# Esquematico_Blue_Pill.net
KiCad netlist of a schematic drawn in EAGLE
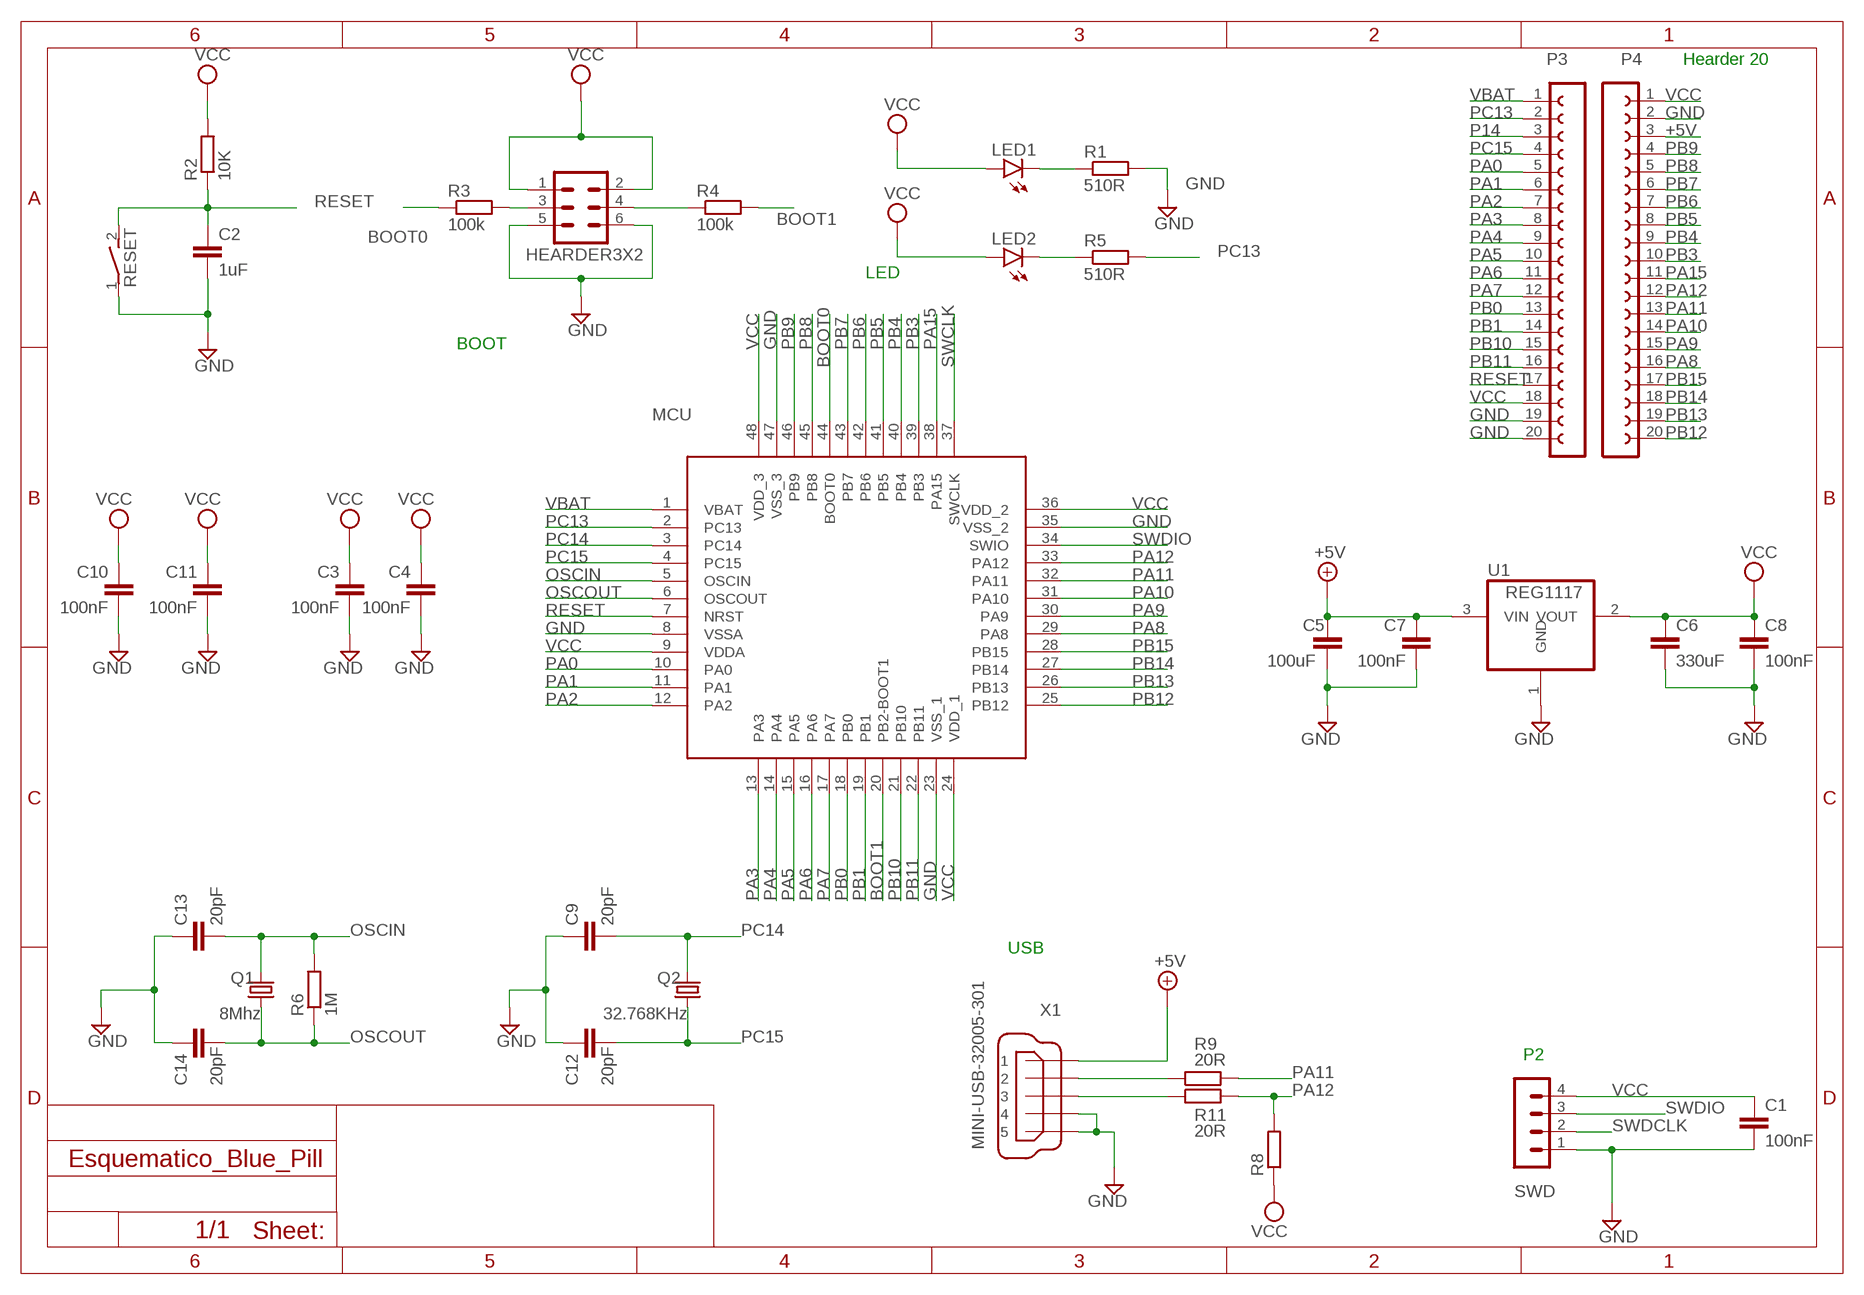
[diagram p0: schematic, sheet 1]

(export (version "E")
  (design (tool "Eeschema 10.0.6"))
  (components
    (comp (ref "C1")
      (value "100nF")
      (footprint "eagle-import:C2.5-2")
      (libsource (lib "eagle-import") (part "C2.5/2"))
    )
    (comp (ref "C2")
      (value "1uF")
      (footprint "eagle-import:C2.5-3")
      (libsource (lib "eagle-import") (part "C2,5-3"))
    )
    (comp (ref "C3")
      (value "100nF")
      (footprint "eagle-import:C2.5-2")
      (libsource (lib "eagle-import") (part "C2.5/2"))
    )
    (comp (ref "C4")
      (value "100nF")
      (footprint "eagle-import:C2.5-2")
      (libsource (lib "eagle-import") (part "C2.5/2"))
    )
    (comp (ref "C5")
      (value "100uF")
      (footprint "eagle-import:C2.5-2")
      (libsource (lib "eagle-import") (part "C2.5/2"))
    )
    (comp (ref "C6")
      (value "330uF")
      (footprint "eagle-import:C2.5-2")
      (libsource (lib "eagle-import") (part "C2.5/2"))
    )
    (comp (ref "C7")
      (value "100nF")
      (footprint "eagle-import:C2.5-2")
      (libsource (lib "eagle-import") (part "C2.5/2"))
    )
    (comp (ref "C8")
      (value "100nF")
      (footprint "eagle-import:C2.5-2")
      (libsource (lib "eagle-import") (part "C2.5/2"))
    )
    (comp (ref "C9")
      (value "20pF")
      (footprint "eagle-import:C2.5-2")
      (libsource (lib "eagle-import") (part "C2.5/2"))
    )
    (comp (ref "C10")
      (value "100nF")
      (footprint "eagle-import:C2.5-2")
      (libsource (lib "eagle-import") (part "C2.5/2"))
    )
    (comp (ref "C11")
      (value "100nF")
      (footprint "eagle-import:C2.5-2")
      (libsource (lib "eagle-import") (part "C2.5/2"))
    )
    (comp (ref "C12")
      (value "20pF")
      (footprint "eagle-import:C2.5-2")
      (libsource (lib "eagle-import") (part "C2.5/2"))
    )
    (comp (ref "C13")
      (value "20pF")
      (footprint "eagle-import:C2.5-2")
      (libsource (lib "eagle-import") (part "C2.5/2"))
    )
    (comp (ref "C14")
      (value "20pF")
      (footprint "eagle-import:C2.5-2")
      (libsource (lib "eagle-import") (part "C2.5/2"))
    )
    (comp (ref "HEARDER3X2")
      (value "MA03-2")
      (footprint "eagle-import:MA03-2")
      (libsource (lib "eagle-import") (part "MA03-2"))
    )
    (comp (ref "LED1")
      (value "LED3MM")
      (footprint "eagle-import:LED3MM")
      (libsource (lib "eagle-import") (part "LED3MM"))
    )
    (comp (ref "LED2")
      (value "LED3MM")
      (footprint "eagle-import:LED3MM")
      (libsource (lib "eagle-import") (part "LED3MM"))
    )
    (comp (ref "MCU")
      (value "STM32F103C8T6F103C8T6")
      (footprint "eagle-import:STM32")
      (libsource (lib "eagle-import") (part "STM32F103C8T6F103C8T6"))
    )
    (comp (ref "P3")
      (value "FE20-1")
      (footprint "eagle-import:FE20")
      (libsource (lib "eagle-import") (part "FE20-1"))
    )
    (comp (ref "P4")
      (value "FE20-1")
      (footprint "eagle-import:FE20")
      (libsource (lib "eagle-import") (part "FE20-1"))
    )
    (comp (ref "Q1")
      (value "8Mhz")
      (footprint "eagle-import:HC49_S")
      (libsource (lib "eagle-import") (part "CRYSTALHC49S"))
    )
    (comp (ref "Q2")
      (value "32.768KHz")
      (footprint "eagle-import:HC49_S")
      (libsource (lib "eagle-import") (part "CRYSTALHC49S"))
    )
    (comp (ref "R1")
      (value "510R")
      (footprint "eagle-import:0204_5")
      (libsource (lib "eagle-import") (part "R-EU_0204/5"))
    )
    (comp (ref "R2")
      (value "10K")
      (footprint "eagle-import:0204_7")
      (libsource (lib "eagle-import") (part "R-EU_0204/7"))
    )
    (comp (ref "R3")
      (value "100k")
      (footprint "eagle-import:0204_5")
      (libsource (lib "eagle-import") (part "R-EU_0204/5"))
    )
    (comp (ref "R4")
      (value "100k")
      (footprint "eagle-import:0204_5")
      (libsource (lib "eagle-import") (part "R-EU_0204/5"))
    )
    (comp (ref "R5")
      (value "510R")
      (footprint "eagle-import:0204_5")
      (libsource (lib "eagle-import") (part "R-EU_0204/5"))
    )
    (comp (ref "R6")
      (value "1M")
      (footprint "eagle-import:0204_5")
      (libsource (lib "eagle-import") (part "R-EU_0204/5"))
    )
    (comp (ref "R8")
      (value "R-EU_0204/5")
      (footprint "eagle-import:0204_5")
      (libsource (lib "eagle-import") (part "R-EU_0204/5"))
    )
    (comp (ref "R9")
      (value "20R")
      (footprint "eagle-import:0204_5")
      (libsource (lib "eagle-import") (part "R-EU_0204/5"))
    )
    (comp (ref "R11")
      (value "20R")
      (footprint "eagle-import:0204_5")
      (libsource (lib "eagle-import") (part "R-EU_0204/5"))
    )
    (comp (ref "RESET")
      (value "DS01E")
      (footprint "eagle-import:DS-01")
      (libsource (lib "eagle-import") (part "DS01E"))
    )
    (comp (ref "SWD")
      (value "MA04-1")
      (footprint "eagle-import:MA04-1")
      (libsource (lib "eagle-import") (part "MA04-1"))
    )
    (comp (ref "U1")
      (value "REG1117")
      (footprint "eagle-import:SOT223")
      (libsource (lib "eagle-import") (part "REG1117"))
    )
    (comp (ref "X1")
      (value "MINI-USB-32005-301")
      (footprint "eagle-import:32005-301")
      (libsource (lib "eagle-import") (part "MINI-USB-32005-301"))
    )
  )
  (nets
    (net (code "1") (name "+5V") (class "Default")
      (node (ref "C5") (pin "1") (pinfunction "1_1") (pintype "passive"))
      (node (ref "C7") (pin "1") (pinfunction "1_1") (pintype "passive"))
      (node (ref "P4") (pin "3") (pinfunction "3_3") (pintype "passive"))
      (node (ref "U1") (pin "3") (pinfunction "VIN_3") (pintype "input"))
      (node (ref "X1") (pin "1") (pinfunction "1_1") (pintype "passive"))
    )
    (net (code "2") (name "/BOOT0") (class "Default")
      (node (ref "MCU") (pin "44") (pinfunction "BOOT0_44") (pintype "bidirectional"))
      (node (ref "R3") (pin "1") (pinfunction "1_1") (pintype "passive"))
    )
    (net (code "3") (name "/BOOT1") (class "Default")
      (node (ref "MCU") (pin "20") (pinfunction "PB2-BOOT1_20") (pintype "bidirectional"))
      (node (ref "R4") (pin "2") (pinfunction "2_2") (pintype "passive"))
    )
    (net (code "4") (name "/OSCIN") (class "Default")
      (node (ref "C13") (pin "2") (pinfunction "2_2") (pintype "passive"))
      (node (ref "MCU") (pin "5") (pinfunction "OSCIN_5") (pintype "bidirectional"))
      (node (ref "Q1") (pin "2") (pinfunction "2_2") (pintype "passive"))
      (node (ref "R6") (pin "2") (pinfunction "2_2") (pintype "passive"))
    )
    (net (code "5") (name "/OSCOUT") (class "Default")
      (node (ref "C14") (pin "2") (pinfunction "2_2") (pintype "passive"))
      (node (ref "MCU") (pin "6") (pinfunction "OSCOUT_6") (pintype "bidirectional"))
      (node (ref "Q1") (pin "1") (pinfunction "1_1") (pintype "passive"))
      (node (ref "R6") (pin "1") (pinfunction "1_1") (pintype "passive"))
    )
    (net (code "6") (name "/P14") (class "Default")
      (node (ref "P3") (pin "3") (pinfunction "3_3") (pintype "passive"))
    )
    (net (code "7") (name "/PA0") (class "Default")
      (node (ref "MCU") (pin "10") (pinfunction "PA0_10") (pintype "bidirectional"))
      (node (ref "P3") (pin "5") (pinfunction "5_5") (pintype "passive"))
    )
    (net (code "8") (name "/PA1") (class "Default")
      (node (ref "MCU") (pin "11") (pinfunction "PA1_11") (pintype "bidirectional"))
      (node (ref "P3") (pin "6") (pinfunction "6_6") (pintype "passive"))
    )
    (net (code "9") (name "/PA2") (class "Default")
      (node (ref "MCU") (pin "12") (pinfunction "PA2_12") (pintype "bidirectional"))
      (node (ref "P3") (pin "7") (pinfunction "7_7") (pintype "passive"))
    )
    (net (code "10") (name "/PA3") (class "Default")
      (node (ref "MCU") (pin "13") (pinfunction "PA3_13") (pintype "bidirectional"))
      (node (ref "P3") (pin "8") (pinfunction "8_8") (pintype "passive"))
    )
    (net (code "11") (name "/PA4") (class "Default")
      (node (ref "MCU") (pin "14") (pinfunction "PA4_14") (pintype "bidirectional"))
      (node (ref "P3") (pin "9") (pinfunction "9_9") (pintype "passive"))
    )
    (net (code "12") (name "/PA5") (class "Default")
      (node (ref "MCU") (pin "15") (pinfunction "PA5_15") (pintype "bidirectional"))
      (node (ref "P3") (pin "10") (pinfunction "10_10") (pintype "passive"))
    )
    (net (code "13") (name "/PA6") (class "Default")
      (node (ref "MCU") (pin "16") (pinfunction "PA6_16") (pintype "bidirectional"))
      (node (ref "P3") (pin "11") (pinfunction "11_11") (pintype "passive"))
    )
    (net (code "14") (name "/PA7") (class "Default")
      (node (ref "MCU") (pin "17") (pinfunction "PA7_17") (pintype "bidirectional"))
      (node (ref "P3") (pin "12") (pinfunction "12_12") (pintype "passive"))
    )
    (net (code "15") (name "/PA8") (class "Default")
      (node (ref "MCU") (pin "29") (pinfunction "PA8_29") (pintype "bidirectional"))
      (node (ref "P4") (pin "16") (pinfunction "16_16") (pintype "passive"))
    )
    (net (code "16") (name "/PA9") (class "Default")
      (node (ref "MCU") (pin "30") (pinfunction "PA9_30") (pintype "bidirectional"))
      (node (ref "P4") (pin "15") (pinfunction "15_15") (pintype "passive"))
    )
    (net (code "17") (name "/PA10") (class "Default")
      (node (ref "MCU") (pin "31") (pinfunction "PA10_31") (pintype "bidirectional"))
      (node (ref "P4") (pin "14") (pinfunction "14_14") (pintype "passive"))
    )
    (net (code "18") (name "/PA11") (class "Default")
      (node (ref "MCU") (pin "32") (pinfunction "PA11_32") (pintype "bidirectional"))
      (node (ref "P4") (pin "13") (pinfunction "13_13") (pintype "passive"))
      (node (ref "R9") (pin "2") (pinfunction "2_2") (pintype "passive"))
    )
    (net (code "19") (name "/PA12") (class "Default")
      (node (ref "MCU") (pin "33") (pinfunction "PA12_33") (pintype "bidirectional"))
      (node (ref "P4") (pin "12") (pinfunction "12_12") (pintype "passive"))
      (node (ref "R11") (pin "2") (pinfunction "2_2") (pintype "passive"))
      (node (ref "R8") (pin "2") (pinfunction "2_2") (pintype "passive"))
    )
    (net (code "20") (name "/PA15") (class "Default")
      (node (ref "MCU") (pin "38") (pinfunction "PA15_38") (pintype "bidirectional"))
      (node (ref "P4") (pin "11") (pinfunction "11_11") (pintype "passive"))
    )
    (net (code "21") (name "/PB0") (class "Default")
      (node (ref "MCU") (pin "18") (pinfunction "PB0_18") (pintype "bidirectional"))
      (node (ref "P3") (pin "13") (pinfunction "13_13") (pintype "passive"))
    )
    (net (code "22") (name "/PB1") (class "Default")
      (node (ref "MCU") (pin "19") (pinfunction "PB1_19") (pintype "bidirectional"))
      (node (ref "P3") (pin "14") (pinfunction "14_14") (pintype "passive"))
    )
    (net (code "23") (name "/PB3") (class "Default")
      (node (ref "MCU") (pin "39") (pinfunction "PB3_39") (pintype "bidirectional"))
      (node (ref "P4") (pin "10") (pinfunction "10_10") (pintype "passive"))
    )
    (net (code "24") (name "/PB4") (class "Default")
      (node (ref "MCU") (pin "40") (pinfunction "PB4_40") (pintype "bidirectional"))
      (node (ref "P4") (pin "9") (pinfunction "9_9") (pintype "passive"))
    )
    (net (code "25") (name "/PB5") (class "Default")
      (node (ref "MCU") (pin "41") (pinfunction "PB5_41") (pintype "bidirectional"))
      (node (ref "P4") (pin "8") (pinfunction "8_8") (pintype "passive"))
    )
    (net (code "26") (name "/PB6") (class "Default")
      (node (ref "MCU") (pin "42") (pinfunction "PB6_42") (pintype "bidirectional"))
      (node (ref "P4") (pin "7") (pinfunction "7_7") (pintype "passive"))
    )
    (net (code "27") (name "/PB7") (class "Default")
      (node (ref "MCU") (pin "43") (pinfunction "PB7_43") (pintype "bidirectional"))
      (node (ref "P4") (pin "6") (pinfunction "6_6") (pintype "passive"))
    )
    (net (code "28") (name "/PB8") (class "Default")
      (node (ref "MCU") (pin "45") (pinfunction "PB8_45") (pintype "bidirectional"))
      (node (ref "P4") (pin "5") (pinfunction "5_5") (pintype "passive"))
    )
    (net (code "29") (name "/PB9") (class "Default")
      (node (ref "MCU") (pin "46") (pinfunction "PB9_46") (pintype "bidirectional"))
      (node (ref "P4") (pin "4") (pinfunction "4_4") (pintype "passive"))
    )
    (net (code "30") (name "/PB10") (class "Default")
      (node (ref "MCU") (pin "21") (pinfunction "PB10_21") (pintype "bidirectional"))
      (node (ref "P3") (pin "15") (pinfunction "15_15") (pintype "passive"))
    )
    (net (code "31") (name "/PB11") (class "Default")
      (node (ref "MCU") (pin "22") (pinfunction "PB11_22") (pintype "bidirectional"))
      (node (ref "P3") (pin "16") (pinfunction "16_16") (pintype "passive"))
    )
    (net (code "32") (name "/PB12") (class "Default")
      (node (ref "MCU") (pin "25") (pinfunction "PB12_25") (pintype "bidirectional"))
      (node (ref "P4") (pin "20") (pinfunction "20_20") (pintype "passive"))
    )
    (net (code "33") (name "/PB13") (class "Default")
      (node (ref "MCU") (pin "26") (pinfunction "PB13_26") (pintype "bidirectional"))
      (node (ref "P4") (pin "19") (pinfunction "19_19") (pintype "passive"))
    )
    (net (code "34") (name "/PB14") (class "Default")
      (node (ref "MCU") (pin "27") (pinfunction "PB14_27") (pintype "bidirectional"))
      (node (ref "P4") (pin "18") (pinfunction "18_18") (pintype "passive"))
    )
    (net (code "35") (name "/PB15") (class "Default")
      (node (ref "MCU") (pin "28") (pinfunction "PB15_28") (pintype "bidirectional"))
      (node (ref "P4") (pin "17") (pinfunction "17_17") (pintype "passive"))
    )
    (net (code "36") (name "/PC13") (class "Default")
      (node (ref "MCU") (pin "2") (pinfunction "PC13_2") (pintype "bidirectional"))
      (node (ref "P3") (pin "2") (pinfunction "2_2") (pintype "passive"))
      (node (ref "R5") (pin "2") (pinfunction "2_2") (pintype "passive"))
    )
    (net (code "37") (name "/PC14") (class "Default")
      (node (ref "C9") (pin "2") (pinfunction "2_2") (pintype "passive"))
      (node (ref "MCU") (pin "3") (pinfunction "PC14_3") (pintype "bidirectional"))
      (node (ref "Q2") (pin "2") (pinfunction "2_2") (pintype "passive"))
    )
    (net (code "38") (name "/PC15") (class "Default")
      (node (ref "C12") (pin "2") (pinfunction "2_2") (pintype "passive"))
      (node (ref "MCU") (pin "4") (pinfunction "PC15_4") (pintype "bidirectional"))
      (node (ref "P3") (pin "4") (pinfunction "4_4") (pintype "passive"))
      (node (ref "Q2") (pin "1") (pinfunction "1_1") (pintype "passive"))
    )
    (net (code "39") (name "/RESET") (class "Default")
      (node (ref "C2") (pin "1") (pinfunction "1_1") (pintype "passive"))
      (node (ref "MCU") (pin "7") (pinfunction "NRST_7") (pintype "bidirectional"))
      (node (ref "P3") (pin "17") (pinfunction "17_17") (pintype "passive"))
      (node (ref "R2") (pin "1") (pinfunction "1_1") (pintype "passive"))
      (node (ref "RESET") (pin "2") (pinfunction "2_2") (pintype "passive"))
    )
    (net (code "40") (name "/SWCLK") (class "Default")
      (node (ref "MCU") (pin "37") (pinfunction "SWCLK_37") (pintype "bidirectional"))
    )
    (net (code "41") (name "/SWDCLK") (class "Default")
      (node (ref "SWD") (pin "2") (pinfunction "2_2") (pintype "passive"))
    )
    (net (code "42") (name "/SWDIO") (class "Default")
      (node (ref "MCU") (pin "34") (pinfunction "SWIO_34") (pintype "bidirectional"))
      (node (ref "SWD") (pin "3") (pinfunction "3_3") (pintype "passive"))
    )
    (net (code "43") (name "/VBAT") (class "Default")
      (node (ref "MCU") (pin "1") (pinfunction "VBAT_1") (pintype "bidirectional"))
      (node (ref "P3") (pin "1") (pinfunction "1_1") (pintype "passive"))
    )
    (net (code "44") (name "GND") (class "Default")
      (node (ref "C1") (pin "2") (pinfunction "2_2") (pintype "passive"))
      (node (ref "C10") (pin "2") (pinfunction "2_2") (pintype "passive"))
      (node (ref "C11") (pin "2") (pinfunction "2_2") (pintype "passive"))
      (node (ref "C12") (pin "1") (pinfunction "1_1") (pintype "passive"))
      (node (ref "C13") (pin "1") (pinfunction "1_1") (pintype "passive"))
      (node (ref "C14") (pin "1") (pinfunction "1_1") (pintype "passive"))
      (node (ref "C2") (pin "2") (pinfunction "2_2") (pintype "passive"))
      (node (ref "C3") (pin "2") (pinfunction "2_2") (pintype "passive"))
      (node (ref "C4") (pin "2") (pinfunction "2_2") (pintype "passive"))
      (node (ref "C5") (pin "2") (pinfunction "2_2") (pintype "passive"))
      (node (ref "C6") (pin "2") (pinfunction "2_2") (pintype "passive"))
      (node (ref "C7") (pin "2") (pinfunction "2_2") (pintype "passive"))
      (node (ref "C8") (pin "2") (pinfunction "2_2") (pintype "passive"))
      (node (ref "C9") (pin "1") (pinfunction "1_1") (pintype "passive"))
      (node (ref "HEARDER3X2") (pin "5") (pinfunction "5_5") (pintype "passive"))
      (node (ref "HEARDER3X2") (pin "6") (pinfunction "6_6") (pintype "passive"))
      (node (ref "MCU") (pin "23") (pinfunction "VSS_1_23") (pintype "bidirectional"))
      (node (ref "MCU") (pin "35") (pinfunction "VSS_2_35") (pintype "bidirectional"))
      (node (ref "MCU") (pin "47") (pinfunction "VSS_3_47") (pintype "bidirectional"))
      (node (ref "MCU") (pin "8") (pinfunction "VSSA_8") (pintype "bidirectional"))
      (node (ref "P3") (pin "19") (pinfunction "19_19") (pintype "passive"))
      (node (ref "P3") (pin "20") (pinfunction "20_20") (pintype "passive"))
      (node (ref "P4") (pin "2") (pinfunction "2_2") (pintype "passive"))
      (node (ref "R1") (pin "2") (pinfunction "2_2") (pintype "passive"))
      (node (ref "RESET") (pin "1") (pinfunction "1_1") (pintype "passive"))
      (node (ref "SWD") (pin "1") (pinfunction "1_1") (pintype "passive"))
      (node (ref "U1") (pin "1") (pinfunction "GND_1") (pintype "power_in"))
      (node (ref "X1") (pin "4") (pinfunction "4_4") (pintype "passive"))
      (node (ref "X1") (pin "5") (pinfunction "5_5") (pintype "passive"))
    )
    (net (code "45") (name "Net-(HEARDER3X2-Pad3)") (class "Default")
      (node (ref "HEARDER3X2") (pin "3") (pinfunction "3_3") (pintype "passive"))
      (node (ref "R3") (pin "2") (pinfunction "2_2") (pintype "passive"))
    )
    (net (code "46") (name "Net-(HEARDER3X2-Pad4)") (class "Default")
      (node (ref "HEARDER3X2") (pin "4") (pinfunction "4_4") (pintype "passive"))
      (node (ref "R4") (pin "1") (pinfunction "1_1") (pintype "passive"))
    )
    (net (code "47") (name "Net-(LED1-C)") (class "Default")
      (node (ref "LED1") (pin "K") (pinfunction "C_K") (pintype "passive"))
      (node (ref "R1") (pin "1") (pinfunction "1_1") (pintype "passive"))
    )
    (net (code "48") (name "Net-(LED2-C)") (class "Default")
      (node (ref "LED2") (pin "K") (pinfunction "C_K") (pintype "passive"))
      (node (ref "R5") (pin "1") (pinfunction "1_1") (pintype "passive"))
    )
    (net (code "49") (name "Net-(R9-Pad1)") (class "Default")
      (node (ref "R9") (pin "1") (pinfunction "1_1") (pintype "passive"))
      (node (ref "X1") (pin "2") (pinfunction "2_2") (pintype "passive"))
    )
    (net (code "50") (name "Net-(R11-Pad1)") (class "Default")
      (node (ref "R11") (pin "1") (pinfunction "1_1") (pintype "passive"))
      (node (ref "X1") (pin "3") (pinfunction "3_3") (pintype "passive"))
    )
    (net (code "51") (name "VCC") (class "Default")
      (node (ref "C1") (pin "1") (pinfunction "1_1") (pintype "passive"))
      (node (ref "C10") (pin "1") (pinfunction "1_1") (pintype "passive"))
      (node (ref "C11") (pin "1") (pinfunction "1_1") (pintype "passive"))
      (node (ref "C3") (pin "1") (pinfunction "1_1") (pintype "passive"))
      (node (ref "C4") (pin "1") (pinfunction "1_1") (pintype "passive"))
      (node (ref "C6") (pin "1") (pinfunction "1_1") (pintype "passive"))
      (node (ref "C8") (pin "1") (pinfunction "1_1") (pintype "passive"))
      (node (ref "HEARDER3X2") (pin "1") (pinfunction "1_1") (pintype "passive"))
      (node (ref "HEARDER3X2") (pin "2") (pinfunction "2_2") (pintype "passive"))
      (node (ref "LED1") (pin "A") (pinfunction "A_A") (pintype "passive"))
      (node (ref "LED2") (pin "A") (pinfunction "A_A") (pintype "passive"))
      (node (ref "MCU") (pin "24") (pinfunction "VDD_1_24") (pintype "bidirectional"))
      (node (ref "MCU") (pin "36") (pinfunction "VDD_2_36") (pintype "bidirectional"))
      (node (ref "MCU") (pin "48") (pinfunction "VDD_3_48") (pintype "bidirectional"))
      (node (ref "MCU") (pin "9") (pinfunction "VDDA_9") (pintype "bidirectional"))
      (node (ref "P3") (pin "18") (pinfunction "18_18") (pintype "passive"))
      (node (ref "P4") (pin "1") (pinfunction "1_1") (pintype "passive"))
      (node (ref "R2") (pin "2") (pinfunction "2_2") (pintype "passive"))
      (node (ref "R8") (pin "1") (pinfunction "1_1") (pintype "passive"))
      (node (ref "SWD") (pin "4") (pinfunction "4_4") (pintype "passive"))
      (node (ref "U1") (pin "2") (pinfunction "VOUT_2") (pintype "output"))
    )
  )
)
